# arduino-shield-xyz-slime-stepper-v1.net
KiCad netlist of a schematic drawn in EAGLE
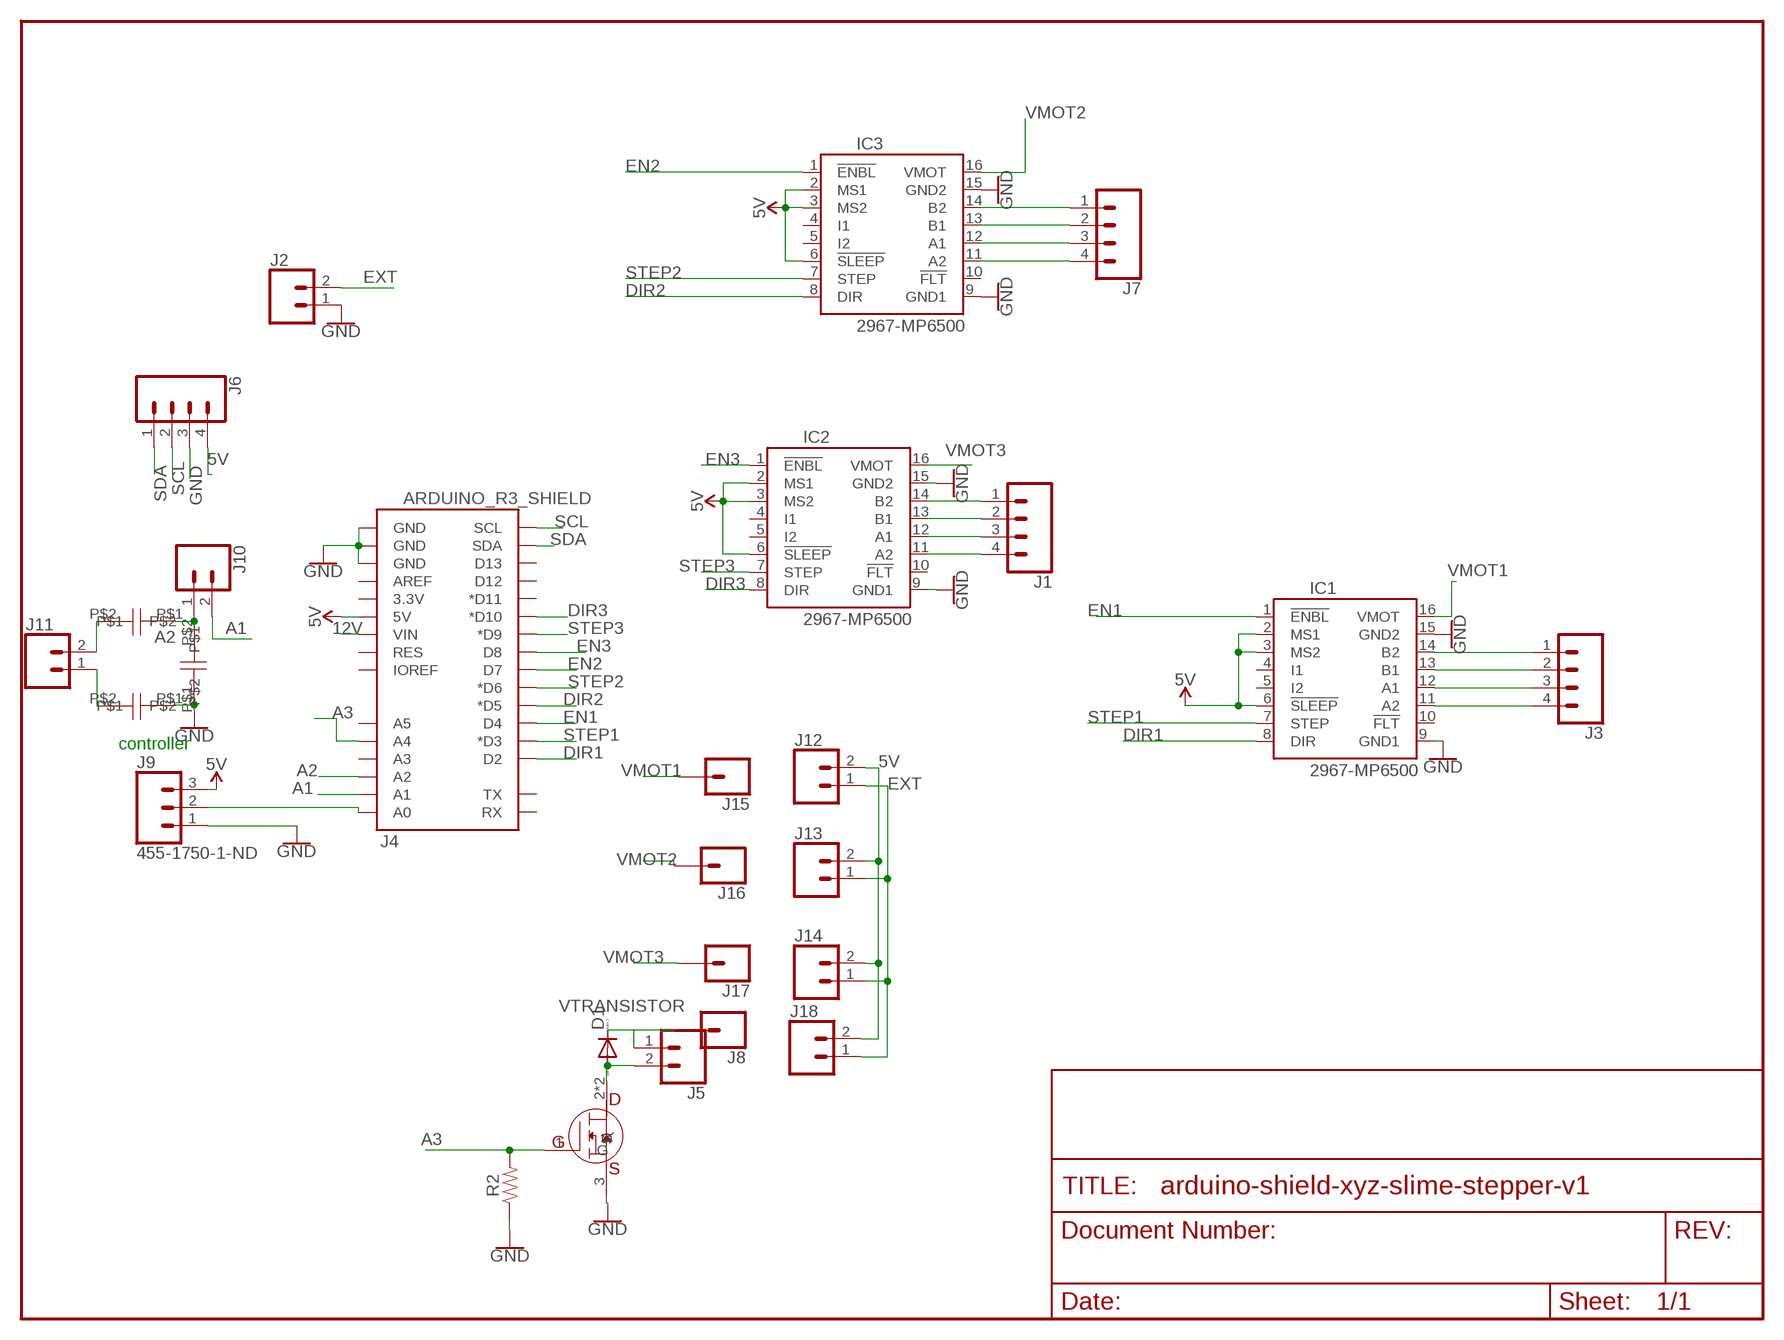
[diagram p0: schematic, sheet 1]

(export (version "E")
  (design (tool "Eeschema 10.0.6"))
  (components
    (comp (ref "D1")
      (value "DIODE-DO-214AC")
      (footprint "eagle-import:DO-214AC")
      (libsource (lib "eagle-import") (part "DIODE-DO-214AC"))
    )
    (comp (ref "IC1")
      (value "2967-MP6500")
      (footprint "eagle-import:MP6500")
      (libsource (lib "eagle-import") (part "2967-MP6500"))
    )
    (comp (ref "IC2")
      (value "2967-MP6500")
      (footprint "eagle-import:MP6500")
      (libsource (lib "eagle-import") (part "2967-MP6500"))
    )
    (comp (ref "IC3")
      (value "2967-MP6500")
      (footprint "eagle-import:MP6500")
      (libsource (lib "eagle-import") (part "2967-MP6500"))
    )
    (comp (ref "J1")
      (value "CONN_04")
      (footprint "eagle-import:1X04")
      (libsource (lib "eagle-import") (part "CONN_04"))
    )
    (comp (ref "J2")
      (value "CONN_02")
      (footprint "eagle-import:1X02")
      (libsource (lib "eagle-import") (part "CONN_02"))
    )
    (comp (ref "J3")
      (value "CONN_04")
      (footprint "eagle-import:1X04")
      (libsource (lib "eagle-import") (part "CONN_04"))
    )
    (comp (ref "J4")
      (value "ARDUINO_R3_SHIELD")
      (footprint "eagle-import:UNO_R3_SHIELD")
      (libsource (lib "eagle-import") (part "ARDUINO_R3_SHIELD"))
    )
    (comp (ref "J5")
      (value "CONN_02")
      (footprint "eagle-import:1X02")
      (libsource (lib "eagle-import") (part "CONN_02"))
    )
    (comp (ref "J6")
      (value "CONN_04")
      (footprint "eagle-import:1X04")
      (libsource (lib "eagle-import") (part "CONN_04"))
    )
    (comp (ref "J7")
      (value "CONN_04")
      (footprint "eagle-import:1X04")
      (libsource (lib "eagle-import") (part "CONN_04"))
    )
    (comp (ref "J8")
      (value "CONN_01")
      (footprint "eagle-import:1X01")
      (libsource (lib "eagle-import") (part "CONN_01"))
    )
    (comp (ref "J9")
      (value "455-1750-1-ND")
      (footprint "eagle-import:1X03")
      (libsource (lib "eagle-import") (part "CONN_03"))
    )
    (comp (ref "J10")
      (value "CONN_02")
      (footprint "eagle-import:1X02")
      (libsource (lib "eagle-import") (part "CONN_02"))
    )
    (comp (ref "J11")
      (value "CONN_02")
      (footprint "eagle-import:1X02")
      (libsource (lib "eagle-import") (part "CONN_02"))
    )
    (comp (ref "J12")
      (value "CONN_02")
      (footprint "eagle-import:1X02")
      (libsource (lib "eagle-import") (part "CONN_02"))
    )
    (comp (ref "J13")
      (value "CONN_02")
      (footprint "eagle-import:1X02")
      (libsource (lib "eagle-import") (part "CONN_02"))
    )
    (comp (ref "J14")
      (value "CONN_02")
      (footprint "eagle-import:1X02")
      (libsource (lib "eagle-import") (part "CONN_02"))
    )
    (comp (ref "J15")
      (value "CONN_01")
      (footprint "eagle-import:1X01")
      (libsource (lib "eagle-import") (part "CONN_01"))
    )
    (comp (ref "J16")
      (value "CONN_01")
      (footprint "eagle-import:1X01")
      (libsource (lib "eagle-import") (part "CONN_01"))
    )
    (comp (ref "J17")
      (value "CONN_01")
      (footprint "eagle-import:1X01")
      (libsource (lib "eagle-import") (part "CONN_01"))
    )
    (comp (ref "J18")
      (value "CONN_02")
      (footprint "eagle-import:1X02")
      (libsource (lib "eagle-import") (part "CONN_02"))
    )
    (comp (ref "R2")
      (value "RESISTORAXIAL-0.3")
      (footprint "eagle-import:AXIAL-0.3")
      (libsource (lib "eagle-import") (part "RESISTORAXIAL-0.3"))
    )
    (comp (ref "U$2")
      (value "AXIALCAP")
      (footprint "eagle-import:AXIALCAP")
      (libsource (lib "eagle-import") (part "AXIALCAP"))
    )
    (comp (ref "U$3")
      (value "AXIALCAP")
      (footprint "eagle-import:AXIALCAP")
      (libsource (lib "eagle-import") (part "AXIALCAP"))
    )
    (comp (ref "U$4")
      (value "AXIALCAP")
      (footprint "eagle-import:AXIALCAP")
      (libsource (lib "eagle-import") (part "AXIALCAP"))
    )
    (comp (ref "U$5")
      (value "IRFL024NPBF")
      (footprint "eagle-import:SOT223")
      (libsource (lib "eagle-import") (part "IRFL024NPBF"))
    )
  )
  (nets
    (net (code "1") (name "/12V") (class "Default")
      (node (ref "J4") (pin "VIN") (pinfunction "VIN_VIN") (pintype "bidirectional"))
    )
    (net (code "2") (name "/A1") (class "Default")
      (node (ref "J10") (pin "2") (pinfunction "2_2") (pintype "passive"))
      (node (ref "J4") (pin "A1") (pinfunction "A1_A1") (pintype "bidirectional"))
    )
    (net (code "3") (name "/A2") (class "Default")
      (node (ref "J10") (pin "1") (pinfunction "1_1") (pintype "passive"))
      (node (ref "J4") (pin "A2") (pinfunction "A2_A2") (pintype "bidirectional"))
      (node (ref "U$3") (pin "P$2") (pinfunction "P$2_P$2") (pintype "bidirectional"))
      (node (ref "U$4") (pin "P$1") (pinfunction "P$1_P$1") (pintype "bidirectional"))
    )
    (net (code "4") (name "/A3") (class "Default")
      (node (ref "J4") (pin "A4") (pinfunction "A4_A4") (pintype "bidirectional"))
      (node (ref "R2") (pin "P$2") (pinfunction "2_P$2") (pintype "passive"))
      (node (ref "U$5") (pin "1") (pinfunction "G_1") (pintype "bidirectional"))
    )
    (net (code "5") (name "/DIR1") (class "Default")
      (node (ref "IC1") (pin "8") (pinfunction "DIR_8") (pintype "input"))
      (node (ref "J4") (pin "D2") (pinfunction "D2_D2") (pintype "bidirectional"))
    )
    (net (code "6") (name "/DIR2") (class "Default")
      (node (ref "IC3") (pin "8") (pinfunction "DIR_8") (pintype "input"))
      (node (ref "J4") (pin "D5") (pinfunction "*D5_D5") (pintype "bidirectional"))
    )
    (net (code "7") (name "/DIR3") (class "Default")
      (node (ref "IC2") (pin "8") (pinfunction "DIR_8") (pintype "input"))
      (node (ref "J4") (pin "D10") (pinfunction "*D10_D10") (pintype "bidirectional"))
    )
    (net (code "8") (name "/EN1") (class "Default")
      (node (ref "IC1") (pin "1") (pinfunction "~{ENBL}_1") (pintype "passive"))
      (node (ref "J4") (pin "D4") (pinfunction "D4_D4") (pintype "bidirectional"))
    )
    (net (code "9") (name "/EN2") (class "Default")
      (node (ref "IC3") (pin "1") (pinfunction "~{ENBL}_1") (pintype "passive"))
      (node (ref "J4") (pin "D7") (pinfunction "D7_D7") (pintype "bidirectional"))
    )
    (net (code "10") (name "/EN3") (class "Default")
      (node (ref "IC2") (pin "1") (pinfunction "~{ENBL}_1") (pintype "passive"))
      (node (ref "J4") (pin "D8") (pinfunction "D8_D8") (pintype "bidirectional"))
    )
    (net (code "11") (name "/EXT") (class "Default")
      (node (ref "J12") (pin "1") (pinfunction "1_1") (pintype "passive"))
      (node (ref "J13") (pin "1") (pinfunction "1_1") (pintype "passive"))
      (node (ref "J14") (pin "1") (pinfunction "1_1") (pintype "passive"))
      (node (ref "J18") (pin "1") (pinfunction "1_1") (pintype "passive"))
      (node (ref "J2") (pin "2") (pinfunction "2_2") (pintype "passive"))
    )
    (net (code "12") (name "/SCL") (class "Default")
      (node (ref "J4") (pin "SCL") (pinfunction "SCL_SCL") (pintype "bidirectional"))
      (node (ref "J6") (pin "2") (pinfunction "2_2") (pintype "passive"))
    )
    (net (code "13") (name "/SDA") (class "Default")
      (node (ref "J4") (pin "SDA") (pinfunction "SDA_SDA") (pintype "bidirectional"))
      (node (ref "J6") (pin "1") (pinfunction "1_1") (pintype "passive"))
    )
    (net (code "14") (name "/STEP1") (class "Default")
      (node (ref "IC1") (pin "7") (pinfunction "STEP_7") (pintype "input"))
      (node (ref "J4") (pin "D3") (pinfunction "*D3_D3") (pintype "bidirectional"))
    )
    (net (code "15") (name "/STEP2") (class "Default")
      (node (ref "IC3") (pin "7") (pinfunction "STEP_7") (pintype "input"))
      (node (ref "J4") (pin "D6") (pinfunction "*D6_D6") (pintype "bidirectional"))
    )
    (net (code "16") (name "/STEP3") (class "Default")
      (node (ref "IC2") (pin "7") (pinfunction "STEP_7") (pintype "input"))
      (node (ref "J4") (pin "D9") (pinfunction "*D9_D9") (pintype "bidirectional"))
    )
    (net (code "17") (name "/VMOT1") (class "Default")
      (node (ref "IC1") (pin "16") (pinfunction "VMOT_16") (pintype "power_in"))
      (node (ref "J15") (pin "1") (pinfunction "1_1") (pintype "passive"))
    )
    (net (code "18") (name "/VMOT2") (class "Default")
      (node (ref "IC3") (pin "16") (pinfunction "VMOT_16") (pintype "power_in"))
      (node (ref "J16") (pin "1") (pinfunction "1_1") (pintype "passive"))
    )
    (net (code "19") (name "/VMOT3") (class "Default")
      (node (ref "IC2") (pin "16") (pinfunction "VMOT_16") (pintype "power_in"))
      (node (ref "J17") (pin "1") (pinfunction "1_1") (pintype "passive"))
    )
    (net (code "20") (name "/VTRANSISTOR") (class "Default")
      (node (ref "D1") (pin "C") (pinfunction "C_C") (pintype "passive"))
      (node (ref "J5") (pin "1") (pinfunction "1_1") (pintype "passive"))
      (node (ref "J8") (pin "1") (pinfunction "1_1") (pintype "passive"))
    )
    (net (code "21") (name "5V") (class "Default")
      (node (ref "IC1") (pin "2") (pinfunction "MS1_2") (pintype "passive"))
      (node (ref "IC1") (pin "3") (pinfunction "MS2_3") (pintype "passive"))
      (node (ref "IC1") (pin "6") (pinfunction "~{SLEEP}_6") (pintype "input"))
      (node (ref "IC2") (pin "2") (pinfunction "MS1_2") (pintype "passive"))
      (node (ref "IC2") (pin "3") (pinfunction "MS2_3") (pintype "passive"))
      (node (ref "IC2") (pin "6") (pinfunction "~{SLEEP}_6") (pintype "input"))
      (node (ref "IC3") (pin "2") (pinfunction "MS1_2") (pintype "passive"))
      (node (ref "IC3") (pin "3") (pinfunction "MS2_3") (pintype "passive"))
      (node (ref "IC3") (pin "6") (pinfunction "~{SLEEP}_6") (pintype "input"))
      (node (ref "J12") (pin "2") (pinfunction "2_2") (pintype "passive"))
      (node (ref "J13") (pin "2") (pinfunction "2_2") (pintype "passive"))
      (node (ref "J14") (pin "2") (pinfunction "2_2") (pintype "passive"))
      (node (ref "J18") (pin "2") (pinfunction "2_2") (pintype "passive"))
      (node (ref "J4") (pin "5V") (pinfunction "5V_5V") (pintype "bidirectional"))
      (node (ref "J6") (pin "4") (pinfunction "4_4") (pintype "passive"))
      (node (ref "J9") (pin "3") (pinfunction "3_3") (pintype "passive"))
    )
    (net (code "22") (name "GND") (class "Default")
      (node (ref "IC1") (pin "15") (pinfunction "GND2_15") (pintype "power_in"))
      (node (ref "IC1") (pin "9") (pinfunction "GND1_9") (pintype "power_in"))
      (node (ref "IC2") (pin "15") (pinfunction "GND2_15") (pintype "power_in"))
      (node (ref "IC2") (pin "9") (pinfunction "GND1_9") (pintype "power_in"))
      (node (ref "IC3") (pin "15") (pinfunction "GND2_15") (pintype "power_in"))
      (node (ref "IC3") (pin "9") (pinfunction "GND1_9") (pintype "power_in"))
      (node (ref "J2") (pin "1") (pinfunction "1_1") (pintype "passive"))
      (node (ref "J4") (pin "GND@0") (pinfunction "GND_GND@0") (pintype "bidirectional"))
      (node (ref "J4") (pin "GND@1") (pinfunction "GND_GND@1") (pintype "bidirectional"))
      (node (ref "J4") (pin "GND@2") (pinfunction "GND_GND@2") (pintype "bidirectional"))
      (node (ref "J6") (pin "3") (pinfunction "3_3") (pintype "passive"))
      (node (ref "J9") (pin "1") (pinfunction "1_1") (pintype "passive"))
      (node (ref "R2") (pin "P$1") (pinfunction "1_P$1") (pintype "passive"))
      (node (ref "U$2") (pin "P$1") (pinfunction "P$1_P$1") (pintype "bidirectional"))
      (node (ref "U$3") (pin "P$1") (pinfunction "P$1_P$1") (pintype "bidirectional"))
      (node (ref "U$5") (pin "3") (pinfunction "S_3") (pintype "bidirectional"))
    )
    (net (code "23") (name "Net-(D1-PadA)") (class "Default")
      (node (ref "D1") (pin "A") (pinfunction "A_A") (pintype "passive"))
      (node (ref "J5") (pin "2") (pinfunction "2_2") (pintype "passive"))
      (node (ref "U$5") (pin "2") (pinfunction "D_2") (pintype "bidirectional"))
      (node (ref "U$5") (pin "4") (pinfunction "D_4") (pintype "bidirectional"))
    )
    (net (code "24") (name "Net-(IC1-A1)") (class "Default")
      (node (ref "IC1") (pin "12") (pinfunction "A1_12") (pintype "output"))
      (node (ref "J3") (pin "3") (pinfunction "3_3") (pintype "passive"))
    )
    (net (code "25") (name "Net-(IC1-A2)") (class "Default")
      (node (ref "IC1") (pin "11") (pinfunction "A2_11") (pintype "output"))
      (node (ref "J3") (pin "4") (pinfunction "4_4") (pintype "passive"))
    )
    (net (code "26") (name "Net-(IC1-B1)") (class "Default")
      (node (ref "IC1") (pin "13") (pinfunction "B1_13") (pintype "output"))
      (node (ref "J3") (pin "2") (pinfunction "2_2") (pintype "passive"))
    )
    (net (code "27") (name "Net-(IC1-B2)") (class "Default")
      (node (ref "IC1") (pin "14") (pinfunction "B2_14") (pintype "output"))
      (node (ref "J3") (pin "1") (pinfunction "1_1") (pintype "passive"))
    )
    (net (code "28") (name "Net-(IC2-A1)") (class "Default")
      (node (ref "IC2") (pin "12") (pinfunction "A1_12") (pintype "output"))
      (node (ref "J1") (pin "3") (pinfunction "3_3") (pintype "passive"))
    )
    (net (code "29") (name "Net-(IC2-A2)") (class "Default")
      (node (ref "IC2") (pin "11") (pinfunction "A2_11") (pintype "output"))
      (node (ref "J1") (pin "4") (pinfunction "4_4") (pintype "passive"))
    )
    (net (code "30") (name "Net-(IC2-B1)") (class "Default")
      (node (ref "IC2") (pin "13") (pinfunction "B1_13") (pintype "output"))
      (node (ref "J1") (pin "2") (pinfunction "2_2") (pintype "passive"))
    )
    (net (code "31") (name "Net-(IC2-B2)") (class "Default")
      (node (ref "IC2") (pin "14") (pinfunction "B2_14") (pintype "output"))
      (node (ref "J1") (pin "1") (pinfunction "1_1") (pintype "passive"))
    )
    (net (code "32") (name "Net-(IC3-A1)") (class "Default")
      (node (ref "IC3") (pin "12") (pinfunction "A1_12") (pintype "output"))
      (node (ref "J7") (pin "3") (pinfunction "3_3") (pintype "passive"))
    )
    (net (code "33") (name "Net-(IC3-A2)") (class "Default")
      (node (ref "IC3") (pin "11") (pinfunction "A2_11") (pintype "output"))
      (node (ref "J7") (pin "4") (pinfunction "4_4") (pintype "passive"))
    )
    (net (code "34") (name "Net-(IC3-B1)") (class "Default")
      (node (ref "IC3") (pin "13") (pinfunction "B1_13") (pintype "output"))
      (node (ref "J7") (pin "2") (pinfunction "2_2") (pintype "passive"))
    )
    (net (code "35") (name "Net-(IC3-B2)") (class "Default")
      (node (ref "IC3") (pin "14") (pinfunction "B2_14") (pintype "output"))
      (node (ref "J7") (pin "1") (pinfunction "1_1") (pintype "passive"))
    )
    (net (code "36") (name "Net-(J4-PadA0)") (class "Default")
      (node (ref "J4") (pin "A0") (pinfunction "A0_A0") (pintype "bidirectional"))
      (node (ref "J9") (pin "2") (pinfunction "2_2") (pintype "passive"))
    )
    (net (code "37") (name "Net-(J11-Pad1)") (class "Default")
      (node (ref "J11") (pin "1") (pinfunction "1_1") (pintype "passive"))
      (node (ref "U$2") (pin "P$2") (pinfunction "P$2_P$2") (pintype "bidirectional"))
    )
    (net (code "38") (name "Net-(J11-Pad2)") (class "Default")
      (node (ref "J11") (pin "2") (pinfunction "2_2") (pintype "passive"))
      (node (ref "U$4") (pin "P$2") (pinfunction "P$2_P$2") (pintype "bidirectional"))
    )
    (net (code "39") (name "unconnected-(IC1-I1-Pad4)") (class "Default")
      (node (ref "IC1") (pin "4") (pinfunction "I1_4") (pintype "passive"))
    )
    (net (code "40") (name "unconnected-(IC1-I2-Pad5)") (class "Default")
      (node (ref "IC1") (pin "5") (pinfunction "I2_5") (pintype "passive"))
    )
    (net (code "41") (name "unconnected-(IC1-~{FLT}-Pad10)") (class "Default")
      (node (ref "IC1") (pin "10") (pinfunction "~{FLT}_10") (pintype "open_collector"))
    )
    (net (code "42") (name "unconnected-(IC2-I1-Pad4)") (class "Default")
      (node (ref "IC2") (pin "4") (pinfunction "I1_4") (pintype "passive"))
    )
    (net (code "43") (name "unconnected-(IC2-I2-Pad5)") (class "Default")
      (node (ref "IC2") (pin "5") (pinfunction "I2_5") (pintype "passive"))
    )
    (net (code "44") (name "unconnected-(IC2-~{FLT}-Pad10)") (class "Default")
      (node (ref "IC2") (pin "10") (pinfunction "~{FLT}_10") (pintype "open_collector"))
    )
    (net (code "45") (name "unconnected-(IC3-I1-Pad4)") (class "Default")
      (node (ref "IC3") (pin "4") (pinfunction "I1_4") (pintype "passive"))
    )
    (net (code "46") (name "unconnected-(IC3-I2-Pad5)") (class "Default")
      (node (ref "IC3") (pin "5") (pinfunction "I2_5") (pintype "passive"))
    )
    (net (code "47") (name "unconnected-(IC3-~{FLT}-Pad10)") (class "Default")
      (node (ref "IC3") (pin "10") (pinfunction "~{FLT}_10") (pintype "open_collector"))
    )
    (net (code "48") (name "unconnected-(J4-*D11-PadD11)") (class "Default")
      (node (ref "J4") (pin "D11") (pinfunction "*D11_D11") (pintype "bidirectional"))
    )
    (net (code "49") (name "unconnected-(J4-Pad3.3V)") (class "Default")
      (node (ref "J4") (pin "3.3V") (pinfunction "3.3V_3.3V") (pintype "bidirectional"))
    )
    (net (code "50") (name "unconnected-(J4-PadA3)") (class "Default")
      (node (ref "J4") (pin "A3") (pinfunction "A3_A3") (pintype "bidirectional"))
    )
    (net (code "51") (name "unconnected-(J4-PadA5)") (class "Default")
      (node (ref "J4") (pin "A5") (pinfunction "A5_A5") (pintype "bidirectional"))
    )
    (net (code "52") (name "unconnected-(J4-PadAREF)") (class "Default")
      (node (ref "J4") (pin "AREF") (pinfunction "AREF_AREF") (pintype "bidirectional"))
    )
    (net (code "53") (name "unconnected-(J4-PadD12)") (class "Default")
      (node (ref "J4") (pin "D12") (pinfunction "D12_D12") (pintype "bidirectional"))
    )
    (net (code "54") (name "unconnected-(J4-PadD13)") (class "Default")
      (node (ref "J4") (pin "D13") (pinfunction "D13_D13") (pintype "bidirectional"))
    )
    (net (code "55") (name "unconnected-(J4-PadIOREF)") (class "Default")
      (node (ref "J4") (pin "IOREF") (pinfunction "IOREF_IOREF") (pintype "bidirectional"))
    )
    (net (code "56") (name "unconnected-(J4-PadRES)") (class "Default")
      (node (ref "J4") (pin "RES") (pinfunction "RES_RES") (pintype "bidirectional"))
    )
    (net (code "57") (name "unconnected-(J4-PadRX)") (class "Default")
      (node (ref "J4") (pin "RX") (pinfunction "RX_RX") (pintype "bidirectional"))
    )
    (net (code "58") (name "unconnected-(J4-PadTX)") (class "Default")
      (node (ref "J4") (pin "TX") (pinfunction "TX_TX") (pintype "bidirectional"))
    )
  )
)
